# Sheet1.net
KiCad netlist of a schematic drawn in Altium Designer
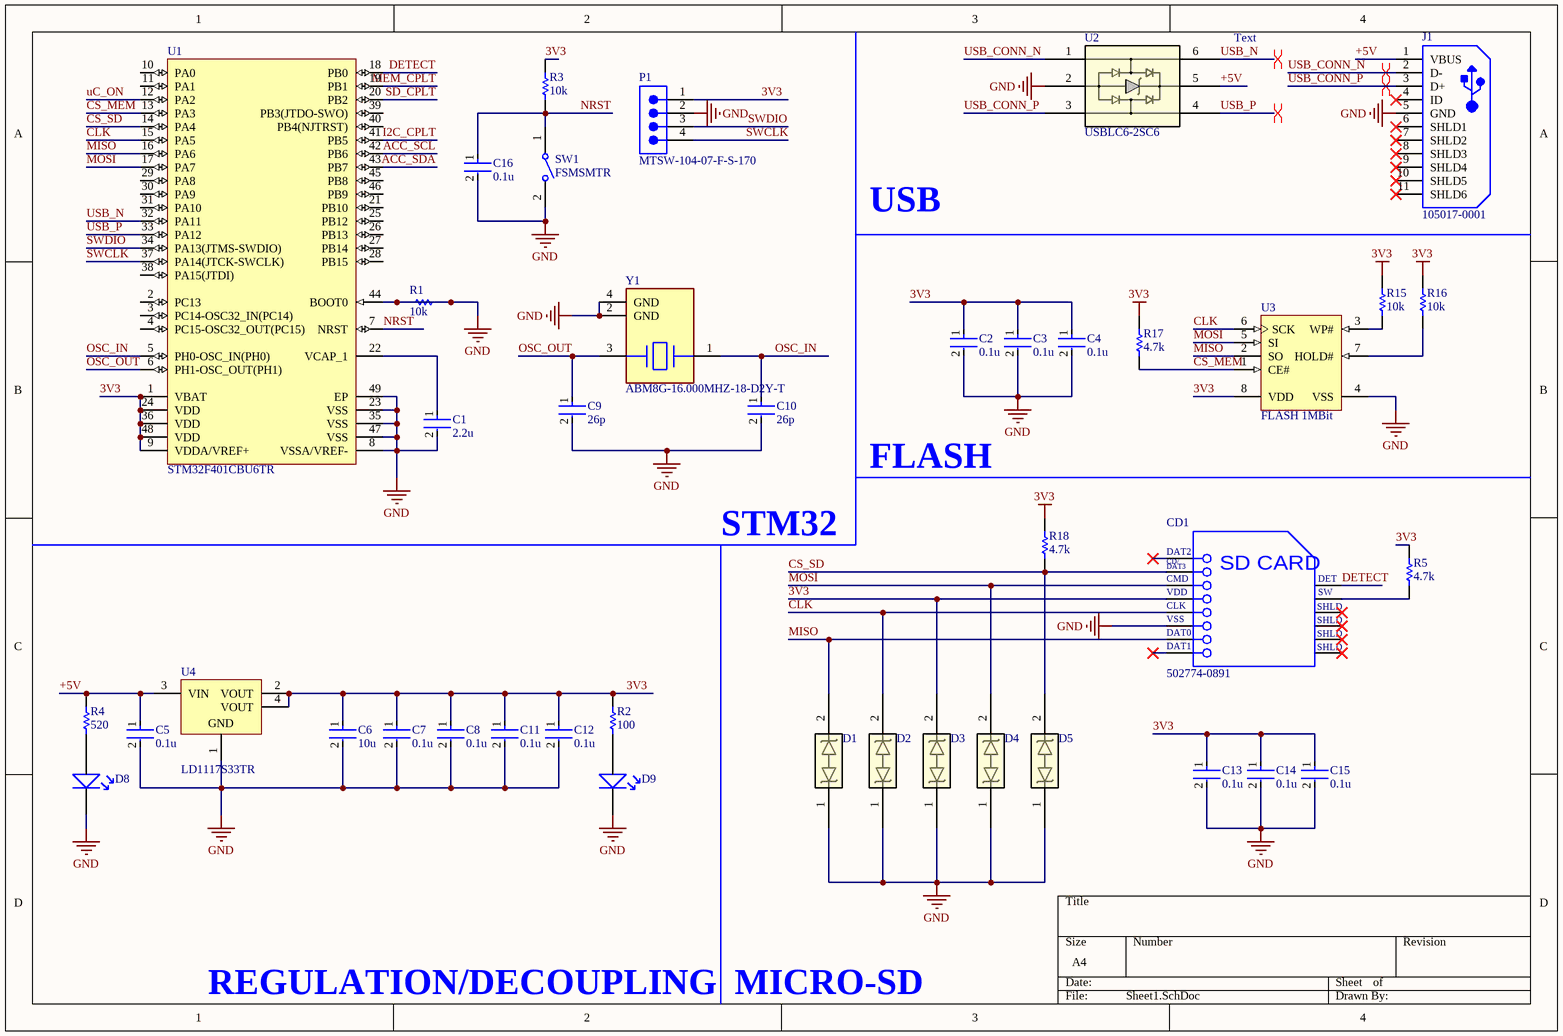
[diagram p0: Sheet1.SchDoc]

(export (version "E")
  (design (tool "Eeschema 10.0.6"))
  (components
    (comp (ref "C1")
      (value "2.2u")
      (footprint "FP-C0603C-CF-MFG")
      (description "CAP CER 0.1UF 50V X7R 0603")
      (fields (field (name "TOLERANCE") "0.1") (field (name "MANUFACTURER") "KEMET"))
      (libsource (lib "Altium Content Vault") (part "b4654b650e69147ec39a6b967a45e02"))
    )
    (comp (ref "C2")
      (value "0.1u")
      (footprint "FP-C0603C-CF-MFG")
      (description "CAP CER 0.1UF 50V X7R 0603")
      (fields (field (name "TOLERANCE") "0.1") (field (name "MANUFACTURER") "KEMET"))
      (libsource (lib "Altium Content Vault") (part "b4654b650e69147ec39a6b967a45e02"))
    )
    (comp (ref "C3")
      (value "0.1u")
      (footprint "FP-C0603C-CF-MFG")
      (description "CAP CER 0.1UF 50V X7R 0603")
      (fields (field (name "TOLERANCE") "0.1") (field (name "MANUFACTURER") "KEMET"))
      (libsource (lib "Altium Content Vault") (part "b4654b650e69147ec39a6b967a45e02"))
    )
    (comp (ref "C4")
      (value "0.1u")
      (footprint "FP-C0603C-CF-MFG")
      (description "CAP CER 0.1UF 50V X7R 0603")
      (fields (field (name "TOLERANCE") "0.1") (field (name "MANUFACTURER") "KEMET"))
      (libsource (lib "Altium Content Vault") (part "b4654b650e69147ec39a6b967a45e02"))
    )
    (comp (ref "C5")
      (value "0.1u")
      (footprint "FP-C0603C-CF-MFG")
      (description "CAP CER 0.1UF 50V X7R 0603")
      (fields (field (name "TOLERANCE") "0.1") (field (name "MANUFACTURER") "KEMET"))
      (libsource (lib "Altium Content Vault") (part "b4654b650e69147ec39a6b967a45e02"))
    )
    (comp (ref "C6")
      (value "10u")
      (footprint "FP-C0603C-CF-MFG")
      (description "CAP CER 0.1UF 50V X7R 0603")
      (fields (field (name "TOLERANCE") "0.1") (field (name "MANUFACTURER") "KEMET"))
      (libsource (lib "Altium Content Vault") (part "b4654b650e69147ec39a6b967a45e02"))
    )
    (comp (ref "C7")
      (value "0.1u")
      (footprint "FP-C0603C-CF-MFG")
      (description "CAP CER 0.1UF 50V X7R 0603")
      (fields (field (name "TOLERANCE") "0.1") (field (name "MANUFACTURER") "KEMET"))
      (libsource (lib "Altium Content Vault") (part "b4654b650e69147ec39a6b967a45e02"))
    )
    (comp (ref "C8")
      (value "0.1u")
      (footprint "FP-C0603C-CF-MFG")
      (description "CAP CER 0.1UF 50V X7R 0603")
      (fields (field (name "TOLERANCE") "0.1") (field (name "MANUFACTURER") "KEMET"))
      (libsource (lib "Altium Content Vault") (part "b4654b650e69147ec39a6b967a45e02"))
    )
    (comp (ref "C9")
      (value "26p")
      (footprint "FP-C0603C-CF-MFG")
      (description "CAP CER 0.1UF 50V X7R 0603")
      (fields (field (name "TOLERANCE") "0.1") (field (name "MANUFACTURER") "KEMET"))
      (libsource (lib "Altium Content Vault") (part "b4654b650e69147ec39a6b967a45e02"))
    )
    (comp (ref "C10")
      (value "26p")
      (footprint "FP-C0603C-CF-MFG")
      (description "CAP CER 0.1UF 50V X7R 0603")
      (fields (field (name "TOLERANCE") "0.1") (field (name "MANUFACTURER") "KEMET"))
      (libsource (lib "Altium Content Vault") (part "b4654b650e69147ec39a6b967a45e02"))
    )
    (comp (ref "C11")
      (value "0.1u")
      (footprint "FP-C0603C-CF-MFG")
      (description "CAP CER 0.1UF 50V X7R 0603")
      (fields (field (name "TOLERANCE") "0.1") (field (name "MANUFACTURER") "KEMET"))
      (libsource (lib "Altium Content Vault") (part "b4654b650e69147ec39a6b967a45e02"))
    )
    (comp (ref "C12")
      (value "0.1u")
      (footprint "FP-C0603C-CF-MFG")
      (description "CAP CER 0.1UF 50V X7R 0603")
      (fields (field (name "TOLERANCE") "0.1") (field (name "MANUFACTURER") "KEMET"))
      (libsource (lib "Altium Content Vault") (part "b4654b650e69147ec39a6b967a45e02"))
    )
    (comp (ref "C13")
      (value "0.1u")
      (footprint "FP-C0603C-CF-MFG")
      (description "CAP CER 0.1UF 50V X7R 0603")
      (fields (field (name "TOLERANCE") "0.1") (field (name "MANUFACTURER") "KEMET"))
      (libsource (lib "Altium Content Vault") (part "b4654b650e69147ec39a6b967a45e02"))
    )
    (comp (ref "C14")
      (value "0.1u")
      (footprint "FP-C0603C-CF-MFG")
      (description "CAP CER 0.1UF 50V X7R 0603")
      (fields (field (name "TOLERANCE") "0.1") (field (name "MANUFACTURER") "KEMET"))
      (libsource (lib "Altium Content Vault") (part "b4654b650e69147ec39a6b967a45e02"))
    )
    (comp (ref "C15")
      (value "0.1u")
      (footprint "FP-C0603C-CF-MFG")
      (description "CAP CER 0.1UF 50V X7R 0603")
      (fields (field (name "TOLERANCE") "0.1") (field (name "MANUFACTURER") "KEMET"))
      (libsource (lib "Altium Content Vault") (part "b4654b650e69147ec39a6b967a45e02"))
    )
    (comp (ref "C16")
      (value "0.1u")
      (footprint "FP-C0603C-CF-MFG")
      (description "CAP CER 0.1UF 50V X7R 0603")
      (fields (field (name "TOLERANCE") "0.1") (field (name "MANUFACTURER") "KEMET"))
      (libsource (lib "Altium Content Vault") (part "b4654b650e69147ec39a6b967a45e02"))
    )
    (comp (ref "CD1")
      (value "502774-0891")
      (footprint "MOLX-502774-0891_V")
      (description "Micro SD Memory Card Connector, 0.5 A, 10 V (DC), -25 to 85 degC, 8-Pin SMT, RoHS, Tape and Reel")
      (fields (field (name "MANUFACTURER") "Molex"))
      (libsource (lib "Altium Content Vault") (part "CN-SD-8-2SW-4S_B"))
    )
    (comp (ref "D1")
      (value "DESD5V0U1BA-7")
      (footprint "SOD-323")
      (description "No Description Available")
      (fields (field (name "COPYRIGHT") "Copyright (C) 2023 Ultra Librarian. All rights reserved."))
      (libsource (lib "DESD5V0U1BA-7") (part "DESD5V0U1BA-7"))
    )
    (comp (ref "D2")
      (value "DESD5V0U1BA-7")
      (footprint "SOD-323")
      (description "No Description Available")
      (fields (field (name "COPYRIGHT") "Copyright (C) 2023 Ultra Librarian. All rights reserved."))
      (libsource (lib "DESD5V0U1BA-7") (part "DESD5V0U1BA-7"))
    )
    (comp (ref "D3")
      (value "DESD5V0U1BA-7")
      (footprint "SOD-323")
      (description "No Description Available")
      (fields (field (name "COPYRIGHT") "Copyright (C) 2023 Ultra Librarian. All rights reserved."))
      (libsource (lib "DESD5V0U1BA-7") (part "DESD5V0U1BA-7"))
    )
    (comp (ref "D4")
      (value "DESD5V0U1BA-7")
      (footprint "SOD-323")
      (description "No Description Available")
      (fields (field (name "COPYRIGHT") "Copyright (C) 2023 Ultra Librarian. All rights reserved."))
      (libsource (lib "DESD5V0U1BA-7") (part "DESD5V0U1BA-7"))
    )
    (comp (ref "D5")
      (value "DESD5V0U1BA-7")
      (footprint "SOD-323")
      (description "No Description Available")
      (fields (field (name "COPYRIGHT") "Copyright (C) 2023 Ultra Librarian. All rights reserved."))
      (libsource (lib "DESD5V0U1BA-7") (part "DESD5V0U1BA-7"))
    )
    (comp (ref "D8") (value "0603 LED") (footprint "0603 LED") (libsource (lib "0603 LED") (part "0603 LED")))
    (comp (ref "D9") (value "0603 LED") (footprint "0603 LED") (libsource (lib "0603 LED") (part "0603 LED")))
    (comp (ref "J1")
      (value "105017-0001")
      (footprint "USB-MICRO-B_V")
      (fields (field (name "MANUFACTURER") "Molex"))
      (libsource (lib "Altium Content Vault") (part "USB-5-6SHLD"))
    )
    (comp (ref "P1")
      (value "MTSW-104-07-F-S-170")
      (footprint "SMTC-MTSW-104-07-X-S-170")
      (fields (field (name "MANUFACTURER") "Samtec"))
      (libsource (lib "Altium Content Vault") (part "SMTC-MTSW-104-07-X-S-170"))
    )
    (comp (ref "R1")
      (value "10k")
      (footprint "RESC1609X50X30NL8T20")
      (description "Chip Resistor, 10 KOhm, +/- 1%, 100 mW, -55 to 155 degC, 0603 (1608 Metric), RoHS, Tape and Reel")
      (fields (field (name "MANUFACTURER") "Vishay Semiconductor"))
      (libsource (lib "Altium Content Vault") (part "RES-2"))
    )
    (comp (ref "R2")
      (value "100")
      (footprint "RESC1609X50X30NL8T20")
      (description "Chip Resistor, 10 KOhm, +/- 1%, 100 mW, -55 to 155 degC, 0603 (1608 Metric), RoHS, Tape and Reel")
      (fields (field (name "MANUFACTURER") "Vishay Semiconductor"))
      (libsource (lib "Altium Content Vault") (part "RES-2"))
    )
    (comp (ref "R3")
      (value "10k")
      (footprint "RESC1609X50X30NL8T20")
      (description "Chip Resistor, 10 KOhm, +/- 1%, 100 mW, -55 to 155 degC, 0603 (1608 Metric), RoHS, Tape and Reel")
      (fields (field (name "MANUFACTURER") "Vishay Semiconductor"))
      (libsource (lib "Altium Content Vault") (part "RES-2"))
    )
    (comp (ref "R4")
      (value "520")
      (footprint "RESC1609X50X30NL8T20")
      (description "Chip Resistor, 10 KOhm, +/- 1%, 100 mW, -55 to 155 degC, 0603 (1608 Metric), RoHS, Tape and Reel")
      (fields (field (name "MANUFACTURER") "Vishay Semiconductor"))
      (libsource (lib "Altium Content Vault") (part "RES-2"))
    )
    (comp (ref "R5")
      (value "4.7k")
      (footprint "RESC1609X50X30NL8T20")
      (description "Chip Resistor, 10 KOhm, +/- 1%, 100 mW, -55 to 155 degC, 0603 (1608 Metric), RoHS, Tape and Reel")
      (fields (field (name "MANUFACTURER") "Vishay Semiconductor"))
      (libsource (lib "Altium Content Vault") (part "RES-2"))
    )
    (comp (ref "R15")
      (value "10k")
      (footprint "RESC1609X50X30NL8T20")
      (description "Chip Resistor, 10 KOhm, +/- 1%, 100 mW, -55 to 155 degC, 0603 (1608 Metric), RoHS, Tape and Reel")
      (fields (field (name "MANUFACTURER") "Vishay Semiconductor"))
      (libsource (lib "Altium Content Vault") (part "RES-2"))
    )
    (comp (ref "R16")
      (value "10k")
      (footprint "RESC1609X50X30NL8T20")
      (description "Chip Resistor, 10 KOhm, +/- 1%, 100 mW, -55 to 155 degC, 0603 (1608 Metric), RoHS, Tape and Reel")
      (fields (field (name "MANUFACTURER") "Vishay Semiconductor"))
      (libsource (lib "Altium Content Vault") (part "RES-2"))
    )
    (comp (ref "R17")
      (value "4.7k")
      (footprint "RESC1609X50X30NL8T20")
      (description "Chip Resistor, 10 KOhm, +/- 1%, 100 mW, -55 to 155 degC, 0603 (1608 Metric), RoHS, Tape and Reel")
      (fields (field (name "MANUFACTURER") "Vishay Semiconductor"))
      (libsource (lib "Altium Content Vault") (part "RES-2"))
    )
    (comp (ref "R18")
      (value "4.7k")
      (footprint "RESC1609X50X30NL8T20")
      (description "Chip Resistor, 10 KOhm, +/- 1%, 100 mW, -55 to 155 degC, 0603 (1608 Metric), RoHS, Tape and Reel")
      (fields (field (name "MANUFACTURER") "Vishay Semiconductor"))
      (libsource (lib "Altium Content Vault") (part "RES-2"))
    )
    (comp (ref "SW1")
      (value "FSMSMTR")
      (footprint "TECO-FSMSMTR_V")
      (description "FSMSM Push Button Switch, 50 mA, -35 to 85 degC, 2-Pin SMD, RoHS, Tape and Reel")
      (fields (field (name "MANUFACTURER") "TE Connectivity"))
      (libsource (lib "Altium Content Vault") (part "SW-SPST-2_C"))
    )
    (comp (ref "U1")
      (value "STM32F401CBU6TR")
      (footprint "UQFN48 P0.5mm")
      (fields (field (name "MANUFACTURER") "STMicroelectronics"))
      (libsource (lib "STM32F401CBU6TR") (part "CMP-0243-00136-1"))
    )
    (comp (ref "U2")
      (value "USBLC6-2SC6")
      (footprint "SOT23-6L_STM")
      (description "No Description Available")
      (fields (field (name "COPYRIGHT") "Copyright (C) 2023 Ultra Librarian. All rights reserved."))
      (libsource (lib "USBLC6-2SC6") (part "USBLC6-2SC6"))
    )
    (comp (ref "U3")
      (value "FLASH 1MBit")
      (footprint "SOIC8 3.9mm")
      (libsource (lib "0603 LED") (part "SST25VF010A-33-4I-SAE"))
    )
    (comp (ref "U4")
      (value "LD1117S33TR")
      (footprint "SOT230P700X180-4N")
      (description "Fixed Positive LDO Regulator, 3.3V, 1.2V Dropout, BIPolar, PDSO4")
      (fields (field (name "MANUFACTURER") "STMicroelectronics"))
      (libsource (lib "0603 LED") (part "LD1117S33TR"))
    )
    (comp (ref "Y1")
      (value "ABM8G-16.000MHZ-18-D2Y-T")
      (footprint "FP-ABM8G-MFG")
      (description "Crystal 16MHz ±20ppm (Tol) ±30ppm (Stability) 18pF FUND 80Ω 4-Pin SMD T/R")
      (fields (field (name "TOLERANCE") "20ppm"))
      (libsource (lib "Altium Content Vault") (part "48e526d86b7f2615d98721063c72f49"))
    )
  )
  (nets
    (net (code "1") (name "/+5V") (class "Default")
      (node (ref "C5") (pin "1") (pinfunction "1_1") (pintype "passive"))
      (node (ref "J1") (pin "1") (pinfunction "VBUS_1") (pintype "passive"))
      (node (ref "R4") (pin "2") (pinfunction "2_2") (pintype "passive"))
      (node (ref "U2") (pin "5") (pinfunction "5_5") (pintype "passive"))
      (node (ref "U4") (pin "3") (pinfunction "VIN_3") (pintype "power_in"))
    )
    (net (code "2") (name "/ACC_SCL") (class "Default")
      (node (ref "U1") (pin "42") (pinfunction "PB6_42") (pintype "bidirectional"))
    )
    (net (code "3") (name "/ACC_SDA") (class "Default")
      (node (ref "U1") (pin "43") (pinfunction "PB7_43") (pintype "bidirectional"))
    )
    (net (code "4") (name "/CLK") (class "Default")
      (node (ref "CD1") (pin "5") (pinfunction "CLK_5") (pintype "passive"))
      (node (ref "D2") (pin "2") (pinfunction "2_2") (pintype "passive"))
      (node (ref "U1") (pin "15") (pinfunction "PA5_15") (pintype "bidirectional"))
      (node (ref "U3") (pin "6") (pinfunction "SCK_6") (pintype "input"))
    )
    (net (code "5") (name "/CS_MEM") (class "Default")
      (node (ref "R17") (pin "1") (pinfunction "1_1") (pintype "passive"))
      (node (ref "U1") (pin "13") (pinfunction "PA3_13") (pintype "bidirectional"))
      (node (ref "U3") (pin "1") (pinfunction "CE#_1") (pintype "input"))
    )
    (net (code "6") (name "/CS_SD") (class "Default")
      (node (ref "CD1") (pin "2") (pinfunction "CD/DAT3_2") (pintype "passive"))
      (node (ref "D5") (pin "2") (pinfunction "2_2") (pintype "passive"))
      (node (ref "R18") (pin "1") (pinfunction "1_1") (pintype "passive"))
      (node (ref "U1") (pin "14") (pinfunction "PA4_14") (pintype "bidirectional"))
    )
    (net (code "7") (name "/DETECT") (class "Default")
      (node (ref "CD1") (pin "9") (pinfunction "DETECT_9") (pintype "passive"))
      (node (ref "U1") (pin "18") (pinfunction "PB0_18") (pintype "bidirectional"))
    )
    (net (code "8") (name "/I2C_CPLT") (class "Default")
      (node (ref "U1") (pin "41") (pinfunction "PB5_41") (pintype "bidirectional"))
    )
    (net (code "9") (name "/MEM_CPLT") (class "Default")
      (node (ref "U1") (pin "19") (pinfunction "PB1_19") (pintype "bidirectional"))
    )
    (net (code "10") (name "/MISO") (class "Default")
      (node (ref "CD1") (pin "7") (pinfunction "DAT0_7") (pintype "passive"))
      (node (ref "D1") (pin "2") (pinfunction "2_2") (pintype "passive"))
      (node (ref "U1") (pin "16") (pinfunction "PA6_16") (pintype "bidirectional"))
      (node (ref "U3") (pin "2") (pinfunction "SO_2") (pintype "tri_state"))
    )
    (net (code "11") (name "/MOSI") (class "Default")
      (node (ref "CD1") (pin "3") (pinfunction "CMD_3") (pintype "passive"))
      (node (ref "D4") (pin "2") (pinfunction "2_2") (pintype "passive"))
      (node (ref "U1") (pin "17") (pinfunction "PA7_17") (pintype "bidirectional"))
      (node (ref "U3") (pin "5") (pinfunction "SI_5") (pintype "input"))
    )
    (net (code "12") (name "/NRST") (class "Default")
      (node (ref "C16") (pin "1") (pinfunction "1_1") (pintype "passive"))
      (node (ref "R3") (pin "2") (pinfunction "2_2") (pintype "passive"))
      (node (ref "SW1") (pin "1") (pinfunction "1_1") (pintype "passive"))
      (node (ref "U1") (pin "7") (pinfunction "NRST_7") (pintype "bidirectional"))
    )
    (net (code "13") (name "/OSC_IN") (class "Default")
      (node (ref "C10") (pin "1") (pinfunction "1_1") (pintype "passive"))
      (node (ref "U1") (pin "5") (pinfunction "PH0-OSC_IN(PH0)_5") (pintype "bidirectional"))
      (node (ref "Y1") (pin "1") (pinfunction "1_1") (pintype "passive"))
    )
    (net (code "14") (name "/OSC_OUT") (class "Default")
      (node (ref "C9") (pin "1") (pinfunction "1_1") (pintype "passive"))
      (node (ref "U1") (pin "6") (pinfunction "PH1-OSC_OUT(PH1)_6") (pintype "bidirectional"))
      (node (ref "Y1") (pin "3") (pinfunction "3_3") (pintype "passive"))
    )
    (net (code "15") (name "/SD_CPLT") (class "Default")
      (node (ref "U1") (pin "20") (pinfunction "PB2_20") (pintype "bidirectional"))
    )
    (net (code "16") (name "/SWCLK") (class "Default")
      (node (ref "P1") (pin "4") (pinfunction "4_4") (pintype "passive"))
      (node (ref "U1") (pin "37") (pinfunction "PA14(JTCK-SWCLK)_37") (pintype "bidirectional"))
    )
    (net (code "17") (name "/SWDIO") (class "Default")
      (node (ref "P1") (pin "3") (pinfunction "3_3") (pintype "passive"))
      (node (ref "U1") (pin "34") (pinfunction "PA13(JTMS-SWDIO)_34") (pintype "bidirectional"))
    )
    (net (code "18") (name "/USB_CONN_N") (class "Default")
      (node (ref "J1") (pin "2") (pinfunction "D-_2") (pintype "passive"))
      (node (ref "U2") (pin "1") (pinfunction "1_1") (pintype "passive"))
    )
    (net (code "19") (name "/USB_CONN_P") (class "Default")
      (node (ref "J1") (pin "3") (pinfunction "D+_3") (pintype "passive"))
      (node (ref "U2") (pin "3") (pinfunction "3_3") (pintype "passive"))
    )
    (net (code "20") (name "/USB_N") (class "Default")
      (node (ref "U1") (pin "32") (pinfunction "PA11_32") (pintype "bidirectional"))
      (node (ref "U2") (pin "6") (pinfunction "6_6") (pintype "passive"))
    )
    (net (code "21") (name "/USB_P") (class "Default")
      (node (ref "U1") (pin "33") (pinfunction "PA12_33") (pintype "bidirectional"))
      (node (ref "U2") (pin "4") (pinfunction "4_4") (pintype "passive"))
    )
    (net (code "22") (name "/uC_ON") (class "Default")
      (node (ref "U1") (pin "12") (pinfunction "PA2_12") (pintype "bidirectional"))
    )
    (net (code "23") (name "3V3") (class "Default")
      (node (ref "C11") (pin "1") (pinfunction "1_1") (pintype "passive"))
      (node (ref "C12") (pin "1") (pinfunction "1_1") (pintype "passive"))
      (node (ref "C13") (pin "1") (pinfunction "1_1") (pintype "passive"))
      (node (ref "C14") (pin "1") (pinfunction "1_1") (pintype "passive"))
      (node (ref "C15") (pin "1") (pinfunction "1_1") (pintype "passive"))
      (node (ref "C2") (pin "1") (pinfunction "1_1") (pintype "passive"))
      (node (ref "C3") (pin "1") (pinfunction "1_1") (pintype "passive"))
      (node (ref "C4") (pin "1") (pinfunction "1_1") (pintype "passive"))
      (node (ref "C6") (pin "1") (pinfunction "1_1") (pintype "passive"))
      (node (ref "C7") (pin "1") (pinfunction "1_1") (pintype "passive"))
      (node (ref "C8") (pin "1") (pinfunction "1_1") (pintype "passive"))
      (node (ref "CD1") (pin "4") (pinfunction "VDD_4") (pintype "passive"))
      (node (ref "D3") (pin "2") (pinfunction "2_2") (pintype "passive"))
      (node (ref "P1") (pin "1") (pinfunction "1_1") (pintype "passive"))
      (node (ref "R15") (pin "2") (pinfunction "2_2") (pintype "passive"))
      (node (ref "R16") (pin "2") (pinfunction "2_2") (pintype "passive"))
      (node (ref "R17") (pin "2") (pinfunction "2_2") (pintype "passive"))
      (node (ref "R18") (pin "2") (pinfunction "2_2") (pintype "passive"))
      (node (ref "R2") (pin "2") (pinfunction "2_2") (pintype "passive"))
      (node (ref "R3") (pin "1") (pinfunction "1_1") (pintype "passive"))
      (node (ref "R5") (pin "2") (pinfunction "2_2") (pintype "passive"))
      (node (ref "U1") (pin "1") (pinfunction "VBAT_1") (pintype "power_in"))
      (node (ref "U1") (pin "24") (pinfunction "VDD_24") (pintype "power_in"))
      (node (ref "U1") (pin "36") (pinfunction "VDD_36") (pintype "power_in"))
      (node (ref "U1") (pin "48") (pinfunction "VDD_48") (pintype "power_in"))
      (node (ref "U1") (pin "9") (pinfunction "VDDA/VREF+_9") (pintype "power_in"))
      (node (ref "U3") (pin "8") (pinfunction "VDD_8") (pintype "power_in"))
      (node (ref "U4") (pin "2") (pinfunction "VOUT_2") (pintype "power_in"))
      (node (ref "U4") (pin "4") (pinfunction "VOUT_4") (pintype "power_in"))
    )
    (net (code "24") (name "GND") (class "Default")
      (node (ref "C1") (pin "2") (pinfunction "2_2") (pintype "passive"))
      (node (ref "C10") (pin "2") (pinfunction "2_2") (pintype "passive"))
      (node (ref "C11") (pin "2") (pinfunction "2_2") (pintype "passive"))
      (node (ref "C12") (pin "2") (pinfunction "2_2") (pintype "passive"))
      (node (ref "C13") (pin "2") (pinfunction "2_2") (pintype "passive"))
      (node (ref "C14") (pin "2") (pinfunction "2_2") (pintype "passive"))
      (node (ref "C15") (pin "2") (pinfunction "2_2") (pintype "passive"))
      (node (ref "C16") (pin "2") (pinfunction "2_2") (pintype "passive"))
      (node (ref "C2") (pin "2") (pinfunction "2_2") (pintype "passive"))
      (node (ref "C3") (pin "2") (pinfunction "2_2") (pintype "passive"))
      (node (ref "C4") (pin "2") (pinfunction "2_2") (pintype "passive"))
      (node (ref "C5") (pin "2") (pinfunction "2_2") (pintype "passive"))
      (node (ref "C6") (pin "2") (pinfunction "2_2") (pintype "passive"))
      (node (ref "C7") (pin "2") (pinfunction "2_2") (pintype "passive"))
      (node (ref "C8") (pin "2") (pinfunction "2_2") (pintype "passive"))
      (node (ref "C9") (pin "2") (pinfunction "2_2") (pintype "passive"))
      (node (ref "CD1") (pin "6") (pinfunction "VSS_6") (pintype "passive"))
      (node (ref "D1") (pin "1") (pinfunction "1_1") (pintype "passive"))
      (node (ref "D2") (pin "1") (pinfunction "1_1") (pintype "passive"))
      (node (ref "D3") (pin "1") (pinfunction "1_1") (pintype "passive"))
      (node (ref "D4") (pin "1") (pinfunction "1_1") (pintype "passive"))
      (node (ref "D5") (pin "1") (pinfunction "1_1") (pintype "passive"))
      (node (ref "D8") (pin "2") (pinfunction "5_2") (pintype "passive"))
      (node (ref "D9") (pin "2") (pinfunction "5_2") (pintype "passive"))
      (node (ref "J1") (pin "5") (pinfunction "GND_5") (pintype "passive"))
      (node (ref "P1") (pin "2") (pinfunction "2_2") (pintype "passive"))
      (node (ref "R1") (pin "1") (pinfunction "1_1") (pintype "passive"))
      (node (ref "R1") (pin "2") (pinfunction "2_2") (pintype "passive"))
      (node (ref "SW1") (pin "2") (pinfunction "2_2") (pintype "passive"))
      (node (ref "U1") (pin "23") (pinfunction "VSS_23") (pintype "power_in"))
      (node (ref "U1") (pin "35") (pinfunction "VSS_35") (pintype "power_in"))
      (node (ref "U1") (pin "44") (pinfunction "BOOT0_44") (pintype "input"))
      (node (ref "U1") (pin "47") (pinfunction "VSS_47") (pintype "power_in"))
      (node (ref "U1") (pin "49") (pinfunction "EP_49") (pintype "power_in"))
      (node (ref "U1") (pin "8") (pinfunction "VSSA/VREF-_8") (pintype "power_in"))
      (node (ref "U2") (pin "2") (pinfunction "2_2") (pintype "passive"))
      (node (ref "U3") (pin "4") (pinfunction "VSS_4") (pintype "power_in"))
      (node (ref "U4") (pin "1") (pinfunction "GND_1") (pintype "power_in"))
      (node (ref "Y1") (pin "2") (pinfunction "GND_2") (pintype "power_in"))
      (node (ref "Y1") (pin "4") (pinfunction "GND_4") (pintype "power_in"))
    )
    (net (code "25") (name "Net-(CD1-SWITCH)") (class "Default")
      (node (ref "CD1") (pin "10") (pinfunction "SWITCH_10") (pintype "passive"))
      (node (ref "R5") (pin "1") (pinfunction "1_1") (pintype "passive"))
    )
    (net (code "26") (name "Net-(D8-6)") (class "Default")
      (node (ref "D8") (pin "1") (pinfunction "6_1") (pintype "passive"))
      (node (ref "R4") (pin "1") (pinfunction "1_1") (pintype "passive"))
    )
    (net (code "27") (name "Net-(D9-6)") (class "Default")
      (node (ref "D9") (pin "1") (pinfunction "6_1") (pintype "passive"))
      (node (ref "R2") (pin "1") (pinfunction "1_1") (pintype "passive"))
    )
    (net (code "28") (name "Net-(U1-VCAP_1)") (class "Default")
      (node (ref "C1") (pin "1") (pinfunction "1_1") (pintype "passive"))
      (node (ref "U1") (pin "22") (pinfunction "VCAP_1_22") (pintype "passive"))
    )
    (net (code "29") (name "Net-(U3-HOLD#)") (class "Default")
      (node (ref "R16") (pin "1") (pinfunction "1_1") (pintype "passive"))
      (node (ref "U3") (pin "7") (pinfunction "HOLD#_7") (pintype "input"))
    )
    (net (code "30") (name "Net-(U3-WP#)") (class "Default")
      (node (ref "R15") (pin "1") (pinfunction "1_1") (pintype "passive"))
      (node (ref "U3") (pin "3") (pinfunction "WP#_3") (pintype "input"))
    )
    (net (code "31") (name "unconnected-(CD1-DAT1-Pad8)") (class "Default")
      (node (ref "CD1") (pin "8") (pinfunction "DAT1_8") (pintype "passive+no_connect"))
    )
    (net (code "32") (name "unconnected-(CD1-DAT2-Pad1)") (class "Default")
      (node (ref "CD1") (pin "1") (pinfunction "DAT2_1") (pintype "passive+no_connect"))
    )
    (net (code "33") (name "unconnected-(CD1-SHLD-Pad11)") (class "Default")
      (node (ref "CD1") (pin "11") (pinfunction "SHLD_11") (pintype "passive+no_connect"))
    )
    (net (code "34") (name "unconnected-(CD1-SHLD-Pad12)") (class "Default")
      (node (ref "CD1") (pin "12") (pinfunction "SHLD_12") (pintype "passive+no_connect"))
    )
    (net (code "35") (name "unconnected-(CD1-SHLD-Pad13)") (class "Default")
      (node (ref "CD1") (pin "13") (pinfunction "SHLD_13") (pintype "passive+no_connect"))
    )
    (net (code "36") (name "unconnected-(CD1-SHLD-Pad14)") (class "Default")
      (node (ref "CD1") (pin "14") (pinfunction "SHLD_14") (pintype "passive+no_connect"))
    )
    (net (code "37") (name "unconnected-(J1-ID-Pad4)") (class "Default")
      (node (ref "J1") (pin "4") (pinfunction "ID_4") (pintype "passive+no_connect"))
    )
    (net (code "38") (name "unconnected-(J1-SHLD1-Pad6)") (class "Default")
      (node (ref "J1") (pin "6") (pinfunction "SHLD1_6") (pintype "passive+no_connect"))
    )
    (net (code "39") (name "unconnected-(J1-SHLD2-Pad7)") (class "Default")
      (node (ref "J1") (pin "7") (pinfunction "SHLD2_7") (pintype "passive+no_connect"))
    )
    (net (code "40") (name "unconnected-(J1-SHLD3-Pad8)") (class "Default")
      (node (ref "J1") (pin "8") (pinfunction "SHLD3_8") (pintype "passive+no_connect"))
    )
    (net (code "41") (name "unconnected-(J1-SHLD4-Pad9)") (class "Default")
      (node (ref "J1") (pin "9") (pinfunction "SHLD4_9") (pintype "passive+no_connect"))
    )
    (net (code "42") (name "unconnected-(J1-SHLD5-Pad10)") (class "Default")
      (node (ref "J1") (pin "10") (pinfunction "SHLD5_10") (pintype "passive+no_connect"))
    )
    (net (code "43") (name "unconnected-(J1-SHLD6-Pad11)") (class "Default")
      (node (ref "J1") (pin "11") (pinfunction "SHLD6_11") (pintype "passive+no_connect"))
    )
    (net (code "44") (name "unconnected-(U1-PA0-Pad10)") (class "Default")
      (node (ref "U1") (pin "10") (pinfunction "PA0_10") (pintype "bidirectional"))
    )
    (net (code "45") (name "unconnected-(U1-PA1-Pad11)") (class "Default")
      (node (ref "U1") (pin "11") (pinfunction "PA1_11") (pintype "bidirectional"))
    )
    (net (code "46") (name "unconnected-(U1-PA8-Pad29)") (class "Default")
      (node (ref "U1") (pin "29") (pinfunction "PA8_29") (pintype "bidirectional"))
    )
    (net (code "47") (name "unconnected-(U1-PA9-Pad30)") (class "Default")
      (node (ref "U1") (pin "30") (pinfunction "PA9_30") (pintype "bidirectional"))
    )
    (net (code "48") (name "unconnected-(U1-PA10-Pad31)") (class "Default")
      (node (ref "U1") (pin "31") (pinfunction "PA10_31") (pintype "bidirectional"))
    )
    (net (code "49") (name "unconnected-(U1-PA15(JTDI)-Pad38)") (class "Default")
      (node (ref "U1") (pin "38") (pinfunction "PA15(JTDI)_38") (pintype "bidirectional"))
    )
    (net (code "50") (name "unconnected-(U1-PB3(JTDO-SWO)-Pad39)") (class "Default")
      (node (ref "U1") (pin "39") (pinfunction "PB3(JTDO-SWO)_39") (pintype "bidirectional"))
    )
    (net (code "51") (name "unconnected-(U1-PB4(NJTRST)-Pad40)") (class "Default")
      (node (ref "U1") (pin "40") (pinfunction "PB4(NJTRST)_40") (pintype "bidirectional"))
    )
    (net (code "52") (name "unconnected-(U1-PB8-Pad45)") (class "Default")
      (node (ref "U1") (pin "45") (pinfunction "PB8_45") (pintype "bidirectional"))
    )
    (net (code "53") (name "unconnected-(U1-PB9-Pad46)") (class "Default")
      (node (ref "U1") (pin "46") (pinfunction "PB9_46") (pintype "bidirectional"))
    )
    (net (code "54") (name "unconnected-(U1-PB10-Pad21)") (class "Default")
      (node (ref "U1") (pin "21") (pinfunction "PB10_21") (pintype "bidirectional"))
    )
    (net (code "55") (name "unconnected-(U1-PB12-Pad25)") (class "Default")
      (node (ref "U1") (pin "25") (pinfunction "PB12_25") (pintype "bidirectional"))
    )
    (net (code "56") (name "unconnected-(U1-PB13-Pad26)") (class "Default")
      (node (ref "U1") (pin "26") (pinfunction "PB13_26") (pintype "bidirectional"))
    )
    (net (code "57") (name "unconnected-(U1-PB14-Pad27)") (class "Default")
      (node (ref "U1") (pin "27") (pinfunction "PB14_27") (pintype "bidirectional"))
    )
    (net (code "58") (name "unconnected-(U1-PB15-Pad28)") (class "Default")
      (node (ref "U1") (pin "28") (pinfunction "PB15_28") (pintype "bidirectional"))
    )
    (net (code "59") (name "unconnected-(U1-PC13-Pad2)") (class "Default")
      (node (ref "U1") (pin "2") (pinfunction "PC13_2") (pintype "bidirectional"))
    )
    (net (code "60") (name "unconnected-(U1-PC14-OSC32_IN(PC14)-Pad3)") (class "Default")
      (node (ref "U1") (pin "3") (pinfunction "PC14-OSC32_IN(PC14)_3") (pintype "bidirectional"))
    )
    (net (code "61") (name "unconnected-(U1-PC15-OSC32_OUT(PC15)-Pad4)") (class "Default")
      (node (ref "U1") (pin "4") (pinfunction "PC15-OSC32_OUT(PC15)_4") (pintype "bidirectional"))
    )
  )
)
